# Rover_Motor_Controller.net
KiCad netlist of a schematic drawn in EAGLE
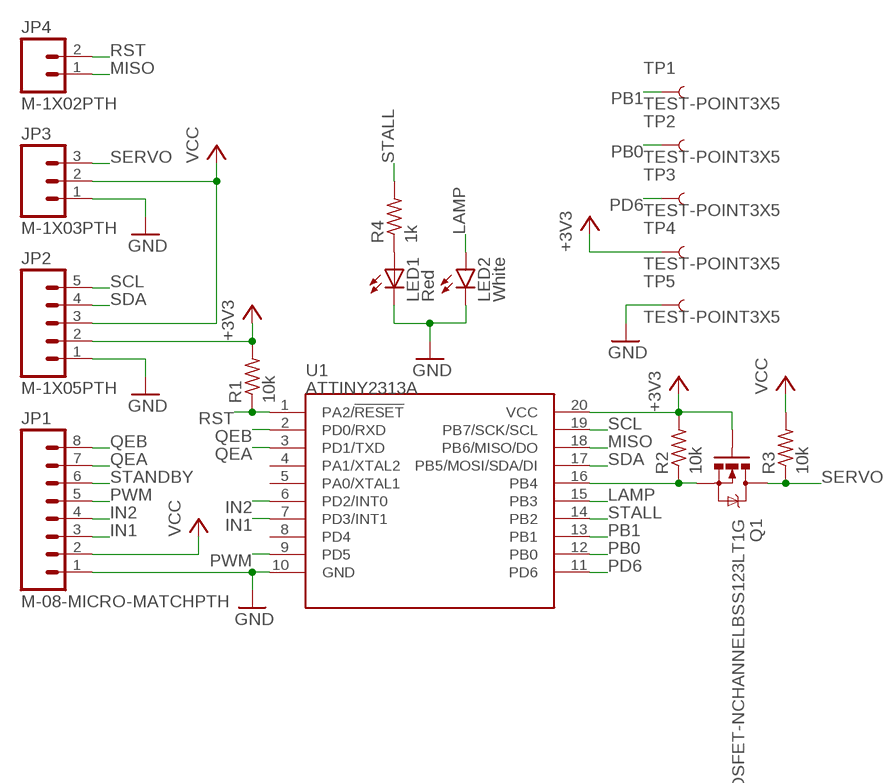
[diagram p0: schematic, sheet 1]

(export (version "E")
  (design (tool "Eeschema 10.0.6"))
  (components
    (comp (ref "JP1")
      (value "M-08-MICRO-MATCHPTH")
      (footprint "eagle-import:M-08-MICRO-MATCH-PTH")
      (libsource (lib "eagle-import") (part "M-08-MICRO-MATCHPTH"))
    )
    (comp (ref "JP2")
      (value "M-1X05PTH")
      (footprint "eagle-import:M-1X05-0.1-PTH")
      (libsource (lib "eagle-import") (part "M-1X05PTH"))
    )
    (comp (ref "JP3")
      (value "M-1X03PTH")
      (footprint "eagle-import:M-1X03-0.1-PTH")
      (libsource (lib "eagle-import") (part "M-1X03PTH"))
    )
    (comp (ref "JP4")
      (value "M-1X02PTH")
      (footprint "eagle-import:M-1X02-0.1-PTH")
      (libsource (lib "eagle-import") (part "M-1X02PTH"))
    )
    (comp (ref "LED1")
      (value "Red")
      (footprint "eagle-import:SML0603")
      (libsource (lib "eagle-import") (part "LEDSML0603"))
    )
    (comp (ref "LED2")
      (value "White")
      (footprint "eagle-import:LED-SMD-RA")
      (libsource (lib "eagle-import") (part "LEDSMD-RA"))
    )
    (comp (ref "Q1")
      (value "MOSFET-NCHANNELBSS123LT1G")
      (footprint "eagle-import:SOT23-3")
      (libsource (lib "eagle-import") (part "MOSFET-NCHANNELBSS123LT1G"))
    )
    (comp (ref "R1")
      (value "10k")
      (footprint "eagle-import:R0603")
      (libsource (lib "eagle-import") (part "R-US_R0603"))
    )
    (comp (ref "R2")
      (value "10k")
      (footprint "eagle-import:R0603")
      (libsource (lib "eagle-import") (part "R-US_R0603"))
    )
    (comp (ref "R3")
      (value "10k")
      (footprint "eagle-import:R0603")
      (libsource (lib "eagle-import") (part "R-US_R0603"))
    )
    (comp (ref "R4")
      (value "1k")
      (footprint "eagle-import:R0603")
      (libsource (lib "eagle-import") (part "R-US_R0603"))
    )
    (comp (ref "TP1")
      (value "TEST-POINT3X5")
      (footprint "eagle-import:PAD.03X.05")
      (libsource (lib "eagle-import") (part "TEST-POINT3X5"))
    )
    (comp (ref "TP2")
      (value "TEST-POINT3X5")
      (footprint "eagle-import:PAD.03X.05")
      (libsource (lib "eagle-import") (part "TEST-POINT3X5"))
    )
    (comp (ref "TP3")
      (value "TEST-POINT3X5")
      (footprint "eagle-import:PAD.03X.05")
      (libsource (lib "eagle-import") (part "TEST-POINT3X5"))
    )
    (comp (ref "TP4")
      (value "TEST-POINT3X5")
      (footprint "eagle-import:PAD.03X.05")
      (libsource (lib "eagle-import") (part "TEST-POINT3X5"))
    )
    (comp (ref "TP5")
      (value "TEST-POINT3X5")
      (footprint "eagle-import:PAD.03X.05")
      (libsource (lib "eagle-import") (part "TEST-POINT3X5"))
    )
    (comp (ref "U1")
      (value "ATTINY2313A")
      (footprint "eagle-import:SOP20W")
      (libsource (lib "eagle-import") (part "ATTINY2313A"))
    )
  )
  (nets
    (net (code "1") (name "+3V3") (class "Default")
      (node (ref "JP2") (pin "2") (pinfunction "2_2") (pintype "passive"))
      (node (ref "Q1") (pin "1") (pinfunction "G_1") (pintype "passive"))
      (node (ref "R1") (pin "2") (pinfunction "2_2") (pintype "passive"))
      (node (ref "R2") (pin "2") (pinfunction "2_2") (pintype "passive"))
      (node (ref "TP4") (pin "P$1") (pinfunction "1_P$1") (pintype "bidirectional"))
      (node (ref "U1") (pin "20") (pinfunction "VCC_20") (pintype "bidirectional"))
    )
    (net (code "2") (name "/IN1") (class "Default")
      (node (ref "JP1") (pin "3") (pinfunction "3_3") (pintype "passive"))
      (node (ref "U1") (pin "7") (pinfunction "PD3/INT1_7") (pintype "bidirectional"))
    )
    (net (code "3") (name "/IN2") (class "Default")
      (node (ref "JP1") (pin "4") (pinfunction "4_4") (pintype "passive"))
      (node (ref "U1") (pin "6") (pinfunction "PD2/INT0_6") (pintype "bidirectional"))
    )
    (net (code "4") (name "/LAMP") (class "Default")
      (node (ref "LED2") (pin "A") (pinfunction "A_A") (pintype "passive"))
      (node (ref "U1") (pin "15") (pinfunction "PB3_15") (pintype "bidirectional"))
    )
    (net (code "5") (name "/MISO") (class "Default")
      (node (ref "JP4") (pin "1") (pinfunction "1_1") (pintype "passive"))
      (node (ref "U1") (pin "18") (pinfunction "PB6/MISO/DO_18") (pintype "bidirectional"))
    )
    (net (code "6") (name "/PB0") (class "Default")
      (node (ref "TP2") (pin "P$1") (pinfunction "1_P$1") (pintype "bidirectional"))
      (node (ref "U1") (pin "12") (pinfunction "PB0_12") (pintype "bidirectional"))
    )
    (net (code "7") (name "/PB1") (class "Default")
      (node (ref "TP1") (pin "P$1") (pinfunction "1_P$1") (pintype "bidirectional"))
      (node (ref "U1") (pin "13") (pinfunction "PB1_13") (pintype "bidirectional"))
    )
    (net (code "8") (name "/PD6") (class "Default")
      (node (ref "TP3") (pin "P$1") (pinfunction "1_P$1") (pintype "bidirectional"))
      (node (ref "U1") (pin "11") (pinfunction "PD6_11") (pintype "bidirectional"))
    )
    (net (code "9") (name "/PWM") (class "Default")
      (node (ref "JP1") (pin "5") (pinfunction "5_5") (pintype "passive"))
      (node (ref "U1") (pin "9") (pinfunction "PD5_9") (pintype "bidirectional"))
    )
    (net (code "10") (name "/QEA") (class "Default")
      (node (ref "JP1") (pin "7") (pinfunction "7_7") (pintype "passive"))
      (node (ref "U1") (pin "3") (pinfunction "PD1/TXD_3") (pintype "bidirectional"))
    )
    (net (code "11") (name "/QEB") (class "Default")
      (node (ref "JP1") (pin "8") (pinfunction "8_8") (pintype "passive"))
      (node (ref "U1") (pin "2") (pinfunction "PD0/RXD_2") (pintype "bidirectional"))
    )
    (net (code "12") (name "/RST") (class "Default")
      (node (ref "JP4") (pin "2") (pinfunction "2_2") (pintype "passive"))
      (node (ref "R1") (pin "1") (pinfunction "1_1") (pintype "passive"))
      (node (ref "U1") (pin "1") (pinfunction "PA2/~{RESET}_1") (pintype "bidirectional"))
    )
    (net (code "13") (name "/SCL") (class "Default")
      (node (ref "JP2") (pin "5") (pinfunction "5_5") (pintype "passive"))
      (node (ref "U1") (pin "19") (pinfunction "PB7/SCK/SCL_19") (pintype "bidirectional"))
    )
    (net (code "14") (name "/SDA") (class "Default")
      (node (ref "JP2") (pin "4") (pinfunction "4_4") (pintype "passive"))
      (node (ref "U1") (pin "17") (pinfunction "PB5/MOSI/SDA/DI_17") (pintype "bidirectional"))
    )
    (net (code "15") (name "/SERVO") (class "Default")
      (node (ref "JP3") (pin "3") (pinfunction "3_3") (pintype "passive"))
      (node (ref "Q1") (pin "3") (pinfunction "D_3") (pintype "passive"))
      (node (ref "R3") (pin "1") (pinfunction "1_1") (pintype "passive"))
    )
    (net (code "16") (name "/STALL") (class "Default")
      (node (ref "R4") (pin "2") (pinfunction "2_2") (pintype "passive"))
      (node (ref "U1") (pin "14") (pinfunction "PB2_14") (pintype "bidirectional"))
    )
    (net (code "17") (name "/STANDBY") (class "Default")
      (node (ref "JP1") (pin "6") (pinfunction "6_6") (pintype "passive"))
    )
    (net (code "18") (name "GND") (class "Default")
      (node (ref "JP1") (pin "1") (pinfunction "1_1") (pintype "passive"))
      (node (ref "JP2") (pin "1") (pinfunction "1_1") (pintype "passive"))
      (node (ref "JP3") (pin "1") (pinfunction "1_1") (pintype "passive"))
      (node (ref "LED1") (pin "C") (pinfunction "C_C") (pintype "passive"))
      (node (ref "LED2") (pin "C") (pinfunction "C_C") (pintype "passive"))
      (node (ref "TP5") (pin "P$1") (pinfunction "1_P$1") (pintype "bidirectional"))
      (node (ref "U1") (pin "10") (pinfunction "GND_10") (pintype "bidirectional"))
    )
    (net (code "19") (name "Net-(LED1-PadA)") (class "Default")
      (node (ref "LED1") (pin "A") (pinfunction "A_A") (pintype "passive"))
      (node (ref "R4") (pin "1") (pinfunction "1_1") (pintype "passive"))
    )
    (net (code "20") (name "Net-(Q1-S)") (class "Default")
      (node (ref "Q1") (pin "2") (pinfunction "S_2") (pintype "passive"))
      (node (ref "R2") (pin "1") (pinfunction "1_1") (pintype "passive"))
      (node (ref "U1") (pin "16") (pinfunction "PB4_16") (pintype "bidirectional"))
    )
    (net (code "21") (name "VCC") (class "Default")
      (node (ref "JP1") (pin "2") (pinfunction "2_2") (pintype "passive"))
      (node (ref "JP2") (pin "3") (pinfunction "3_3") (pintype "passive"))
      (node (ref "JP3") (pin "2") (pinfunction "2_2") (pintype "passive"))
      (node (ref "R3") (pin "2") (pinfunction "2_2") (pintype "passive"))
    )
    (net (code "22") (name "unconnected-(U1-PA0{slash}XTAL1-Pad5)") (class "Default")
      (node (ref "U1") (pin "5") (pinfunction "PA0/XTAL1_5") (pintype "bidirectional"))
    )
    (net (code "23") (name "unconnected-(U1-PA1{slash}XTAL2-Pad4)") (class "Default")
      (node (ref "U1") (pin "4") (pinfunction "PA1/XTAL2_4") (pintype "bidirectional"))
    )
    (net (code "24") (name "unconnected-(U1-PD4-Pad8)") (class "Default")
      (node (ref "U1") (pin "8") (pinfunction "PD4_8") (pintype "bidirectional"))
    )
  )
)
